# Attenuator.net
KiCad netlist of a schematic drawn in Altium Designer
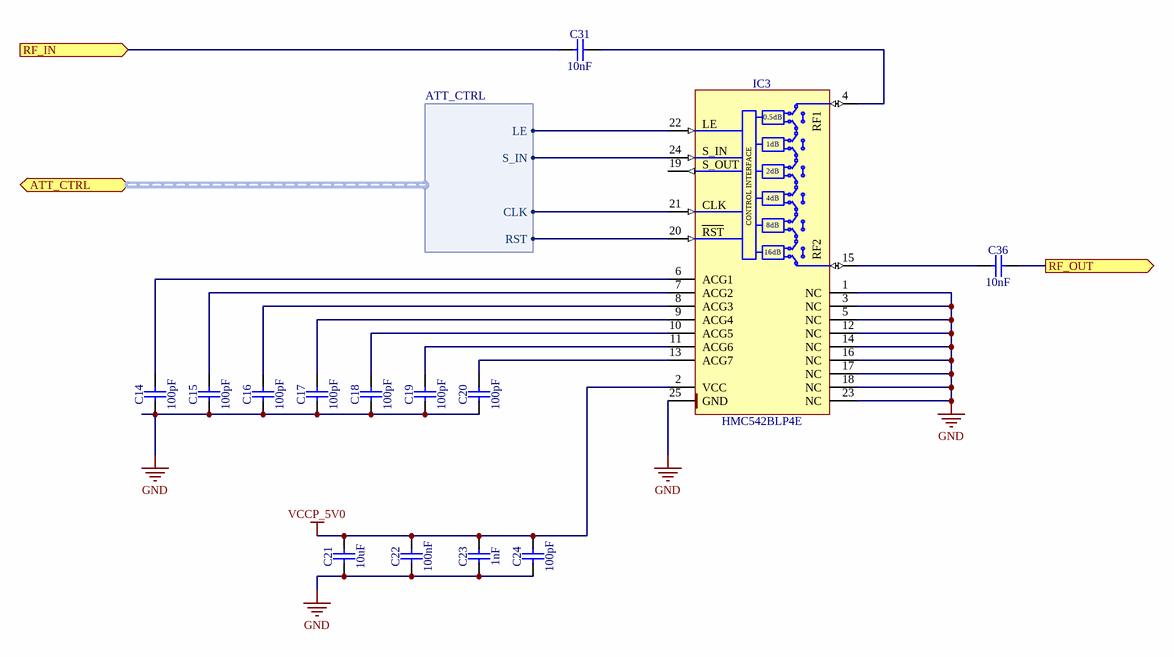
[diagram p0: Attenuator.SchDoc]

(export (version "E")
  (design (tool "Eeschema 10.0.6"))
  (components
    (comp (ref "C14")
      (value "100pF")
      (footprint "CAPC1005X55N")
      (description "Non-polarised capacitor")
      (fields
        (field (name "PART NUMBER") "CC0402_100PF_50V_5%_C0G")
        (field (name "VOLTAGE") "50V")
        (field (name "AUTHOR") "CERN DEM JLC")
      )
      (libsource (lib "Capacitors") (part "Capacitor - non polarized"))
    )
    (comp (ref "C15")
      (value "100pF")
      (footprint "CAPC1005X55N")
      (description "Non-polarised capacitor")
      (fields
        (field (name "PART NUMBER") "CC0402_100PF_50V_5%_C0G")
        (field (name "VOLTAGE") "50V")
        (field (name "AUTHOR") "CERN DEM JLC")
      )
      (libsource (lib "Capacitors") (part "Capacitor - non polarized"))
    )
    (comp (ref "C16")
      (value "100pF")
      (footprint "CAPC1005X55N")
      (description "Non-polarised capacitor")
      (fields
        (field (name "PART NUMBER") "CC0402_100PF_50V_5%_C0G")
        (field (name "VOLTAGE") "50V")
        (field (name "AUTHOR") "CERN DEM JLC")
      )
      (libsource (lib "Capacitors") (part "Capacitor - non polarized"))
    )
    (comp (ref "C17")
      (value "100pF")
      (footprint "CAPC1005X55N")
      (description "Non-polarised capacitor")
      (fields
        (field (name "PART NUMBER") "CC0402_100PF_50V_5%_C0G")
        (field (name "VOLTAGE") "50V")
        (field (name "AUTHOR") "CERN DEM JLC")
      )
      (libsource (lib "Capacitors") (part "Capacitor - non polarized"))
    )
    (comp (ref "C18")
      (value "100pF")
      (footprint "CAPC1005X55N")
      (description "Non-polarised capacitor")
      (fields
        (field (name "PART NUMBER") "CC0402_100PF_50V_5%_C0G")
        (field (name "VOLTAGE") "50V")
        (field (name "AUTHOR") "CERN DEM JLC")
      )
      (libsource (lib "Capacitors") (part "Capacitor - non polarized"))
    )
    (comp (ref "C19")
      (value "100pF")
      (footprint "CAPC1005X55N")
      (description "Non-polarised capacitor")
      (fields
        (field (name "PART NUMBER") "CC0402_100PF_50V_5%_C0G")
        (field (name "VOLTAGE") "50V")
        (field (name "AUTHOR") "CERN DEM JLC")
      )
      (libsource (lib "Capacitors") (part "Capacitor - non polarized"))
    )
    (comp (ref "C20")
      (value "100pF")
      (footprint "CAPC1005X55N")
      (description "Non-polarised capacitor")
      (fields
        (field (name "PART NUMBER") "CC0402_100PF_50V_5%_C0G")
        (field (name "VOLTAGE") "50V")
        (field (name "AUTHOR") "CERN DEM JLC")
      )
      (libsource (lib "Capacitors") (part "Capacitor - non polarized"))
    )
    (comp (ref "C21")
      (value "10uF")
      (footprint "CAPC1608X80N")
      (description "Non-polarised capacitor")
      (fields
        (field (name "PART NUMBER") "CC0603_10UF_16V_20%_X5R")
        (field (name "VOLTAGE") "16V")
        (field (name "AUTHOR") "CERN DEM MR")
      )
      (libsource (lib "Capacitors") (part "Capacitor - non polarized"))
    )
    (comp (ref "C22")
      (value "100nF")
      (footprint "CAPC1005X55N")
      (description "Non-polarised capacitor")
      (fields
        (field (name "PART NUMBER") "CC0402_100NF_16V_10%_X7R")
        (field (name "VOLTAGE") "16V")
        (field (name "AUTHOR") "CERN DEM JLC")
      )
      (libsource (lib "Capacitors") (part "Capacitor - non polarized"))
    )
    (comp (ref "C23")
      (value "1nF")
      (footprint "CAPC1005X55N")
      (description "Non-polarised capacitor")
      (fields
        (field (name "PART NUMBER") "CC0402_1NF_50V_10%_X7R")
        (field (name "VOLTAGE") "50V")
        (field (name "AUTHOR") "CERN DEM JLC")
      )
      (libsource (lib "Capacitors") (part "Capacitor - non polarized"))
    )
    (comp (ref "C24")
      (value "100pF")
      (footprint "CAPC1005X55N")
      (description "Non-polarised capacitor")
      (fields
        (field (name "PART NUMBER") "CC0402_100PF_50V_5%_C0G")
        (field (name "VOLTAGE") "50V")
        (field (name "AUTHOR") "CERN DEM JLC")
      )
      (libsource (lib "Capacitors") (part "Capacitor - non polarized"))
    )
    (comp (ref "C31")
      (value "10nF")
      (footprint "CAPC1005X55N")
      (description "Non-polarised capacitor")
      (fields
        (field (name "PART NUMBER") "CC0402_10NF_16V_10%_X7R")
        (field (name "VOLTAGE") "16V")
        (field (name "AUTHOR") "CERN DEM JLC")
      )
      (libsource (lib "Capacitors") (part "Capacitor - non polarized"))
    )
    (comp (ref "C36")
      (value "10nF")
      (footprint "CAPC1005X55N")
      (description "Non-polarised capacitor")
      (fields
        (field (name "PART NUMBER") "CC0402_10NF_16V_10%_X7R")
        (field (name "VOLTAGE") "16V")
        (field (name "AUTHOR") "CERN DEM JLC")
      )
      (libsource (lib "Capacitors") (part "Capacitor - non polarized"))
    )
    (comp (ref "IC3")
      (value "HMC542BLP4E")
      (footprint "QFN50P400X400X100-25N-S295")
      (description "0.5dB LSB GaAs MMIC 6-bit Digital Serial Control Attenuator, DC - 4GHz")
      (fields (field (name "MANUFACTURER") "HITTITE MICROWAVE CORP") (field (name "AUTHOR") "CERN DEM JMW"))
      (libsource (lib "ICs And Semiconductors") (part "HMC542BLP4E"))
    )
  )
  (nets
    (net (code "2") (name "/CLK") (class "Default")
      (node (ref "IC3") (pin "21") (pinfunction "SHIFT_CLOCK_21") (pintype "input"))
    )
    (net (code "3") (name "/LE") (class "Default")
      (node (ref "IC3") (pin "22") (pinfunction "LATCH_ENABLE_22") (pintype "input"))
    )
    (net (code "4") (name "/RF_IN") (class "Default")
      (node (ref "C31") (pin "1") (pinfunction "1_1") (pintype "passive"))
    )
    (net (code "5") (name "/RF_OUT") (class "Default")
      (node (ref "C36") (pin "2") (pinfunction "2_2") (pintype "passive"))
    )
    (net (code "6") (name "/RST") (class "Default")
      (node (ref "IC3") (pin "20") (pinfunction "~{RESET}_20") (pintype "input"))
    )
    (net (code "7") (name "/S_IN") (class "Default")
      (node (ref "IC3") (pin "24") (pinfunction "SERIAL_INPUT_24") (pintype "input"))
    )
    (net (code "9") (name "GND") (class "Default")
      (node (ref "C14") (pin "1") (pinfunction "1_1") (pintype "passive"))
      (node (ref "C15") (pin "1") (pinfunction "1_1") (pintype "passive"))
      (node (ref "C16") (pin "1") (pinfunction "1_1") (pintype "passive"))
      (node (ref "C17") (pin "1") (pinfunction "1_1") (pintype "passive"))
      (node (ref "C18") (pin "1") (pinfunction "1_1") (pintype "passive"))
      (node (ref "C19") (pin "1") (pinfunction "1_1") (pintype "passive"))
      (node (ref "C20") (pin "1") (pinfunction "1_1") (pintype "passive"))
      (node (ref "C21") (pin "1") (pinfunction "1_1") (pintype "passive"))
      (node (ref "C22") (pin "1") (pinfunction "1_1") (pintype "passive"))
      (node (ref "C23") (pin "1") (pinfunction "1_1") (pintype "passive"))
      (node (ref "C24") (pin "1") (pinfunction "1_1") (pintype "passive"))
      (node (ref "IC3") (pin "1") (pinfunction "NC_1") (pintype "passive"))
      (node (ref "IC3") (pin "12") (pinfunction "NC_12") (pintype "passive"))
      (node (ref "IC3") (pin "14") (pinfunction "NC_14") (pintype "passive"))
      (node (ref "IC3") (pin "16") (pinfunction "NC_16") (pintype "passive"))
      (node (ref "IC3") (pin "17") (pinfunction "NC_17") (pintype "passive"))
      (node (ref "IC3") (pin "18") (pinfunction "NC_18") (pintype "passive"))
      (node (ref "IC3") (pin "23") (pinfunction "NC_23") (pintype "passive"))
      (node (ref "IC3") (pin "25") (pinfunction "GND_25") (pintype "power_in"))
      (node (ref "IC3") (pin "3") (pinfunction "NC_3") (pintype "passive"))
      (node (ref "IC3") (pin "5") (pinfunction "NC_5") (pintype "passive"))
    )
    (net (code "10") (name "Net-(IC3-ACG1)") (class "Default")
      (node (ref "C14") (pin "2") (pinfunction "2_2") (pintype "passive"))
      (node (ref "IC3") (pin "6") (pinfunction "ACG1_6") (pintype "passive"))
    )
    (net (code "11") (name "Net-(IC3-ACG2)") (class "Default")
      (node (ref "C15") (pin "2") (pinfunction "2_2") (pintype "passive"))
      (node (ref "IC3") (pin "7") (pinfunction "ACG2_7") (pintype "passive"))
    )
    (net (code "12") (name "Net-(IC3-ACG3)") (class "Default")
      (node (ref "C16") (pin "2") (pinfunction "2_2") (pintype "passive"))
      (node (ref "IC3") (pin "8") (pinfunction "ACG3_8") (pintype "passive"))
    )
    (net (code "13") (name "Net-(IC3-ACG4)") (class "Default")
      (node (ref "C17") (pin "2") (pinfunction "2_2") (pintype "passive"))
      (node (ref "IC3") (pin "9") (pinfunction "ACG4_9") (pintype "passive"))
    )
    (net (code "14") (name "Net-(IC3-ACG5)") (class "Default")
      (node (ref "C18") (pin "2") (pinfunction "2_2") (pintype "passive"))
      (node (ref "IC3") (pin "10") (pinfunction "ACG5_10") (pintype "passive"))
    )
    (net (code "15") (name "Net-(IC3-ACG6)") (class "Default")
      (node (ref "C19") (pin "2") (pinfunction "2_2") (pintype "passive"))
      (node (ref "IC3") (pin "11") (pinfunction "ACG6_11") (pintype "passive"))
    )
    (net (code "16") (name "Net-(IC3-ACG7)") (class "Default")
      (node (ref "C20") (pin "2") (pinfunction "2_2") (pintype "passive"))
      (node (ref "IC3") (pin "13") (pinfunction "ACG7_13") (pintype "passive"))
    )
    (net (code "17") (name "Net-(IC3-RF1)") (class "Default")
      (node (ref "C31") (pin "2") (pinfunction "2_2") (pintype "passive"))
      (node (ref "IC3") (pin "4") (pinfunction "RF1_4") (pintype "bidirectional"))
    )
    (net (code "18") (name "Net-(IC3-RF2)") (class "Default")
      (node (ref "C36") (pin "1") (pinfunction "1_1") (pintype "passive"))
      (node (ref "IC3") (pin "15") (pinfunction "RF2_15") (pintype "bidirectional"))
    )
    (net (code "19") (name "VCCP_5V0") (class "Default")
      (node (ref "C21") (pin "2") (pinfunction "2_2") (pintype "passive"))
      (node (ref "C22") (pin "2") (pinfunction "2_2") (pintype "passive"))
      (node (ref "C23") (pin "2") (pinfunction "2_2") (pintype "passive"))
      (node (ref "C24") (pin "2") (pinfunction "2_2") (pintype "passive"))
      (node (ref "IC3") (pin "2") (pinfunction "VCC_2") (pintype "power_in"))
    )
    (net (code "20") (name "unconnected-(IC3-SERIAL_OUTPUT-Pad19)") (class "Default")
      (node (ref "IC3") (pin "19") (pinfunction "SERIAL_OUTPUT_19") (pintype "output"))
    )
  )
)
